# Trace_3.net
KiCad netlist of a schematic drawn in Altium Designer
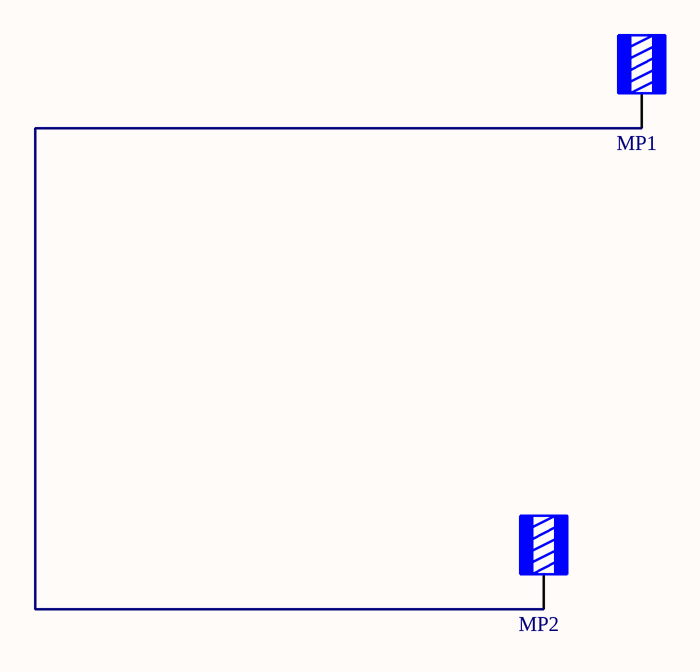
[diagram p0: Trace_3.SchDoc]

(export (version "E")
  (design (tool "Eeschema 10.0.6"))
  (components
    (comp (ref "MP1")
      (value "74651194R")
      (footprint "WURTH 74651194")
      (description "TERM REDCUBE 9PIN PCB")
      (fields (field (name "MANUFACTURER") "Würth Elektronik"))
      (libsource (lib "Celestial Altium Library - altium_library") (part "MOUNTING POINT"))
    )
    (comp (ref "MP2")
      (value "74650074R")
      (footprint "WURTH 74650074")
      (description "TERM REDCUBE M4 4PIN PCB")
      (fields (field (name "MANUFACTURER") "Würth Elektronik"))
      (libsource (lib "Celestial Altium Library - altium_library") (part "MOUNTING POINT"))
    )
  )
  (nets
    (net (code "1") (name "Net-(MP1-Pad1)") (class "Default")
      (node (ref "MP1") (pin "1") (pinfunction "1_1") (pintype "passive"))
      (node (ref "MP2") (pin "1") (pinfunction "1_1") (pintype "passive"))
    )
  )
)
